# Adafruit_E-Ink_Bonnet_for_Raspberry_Pi_r.net
KiCad netlist of a schematic drawn in EAGLE
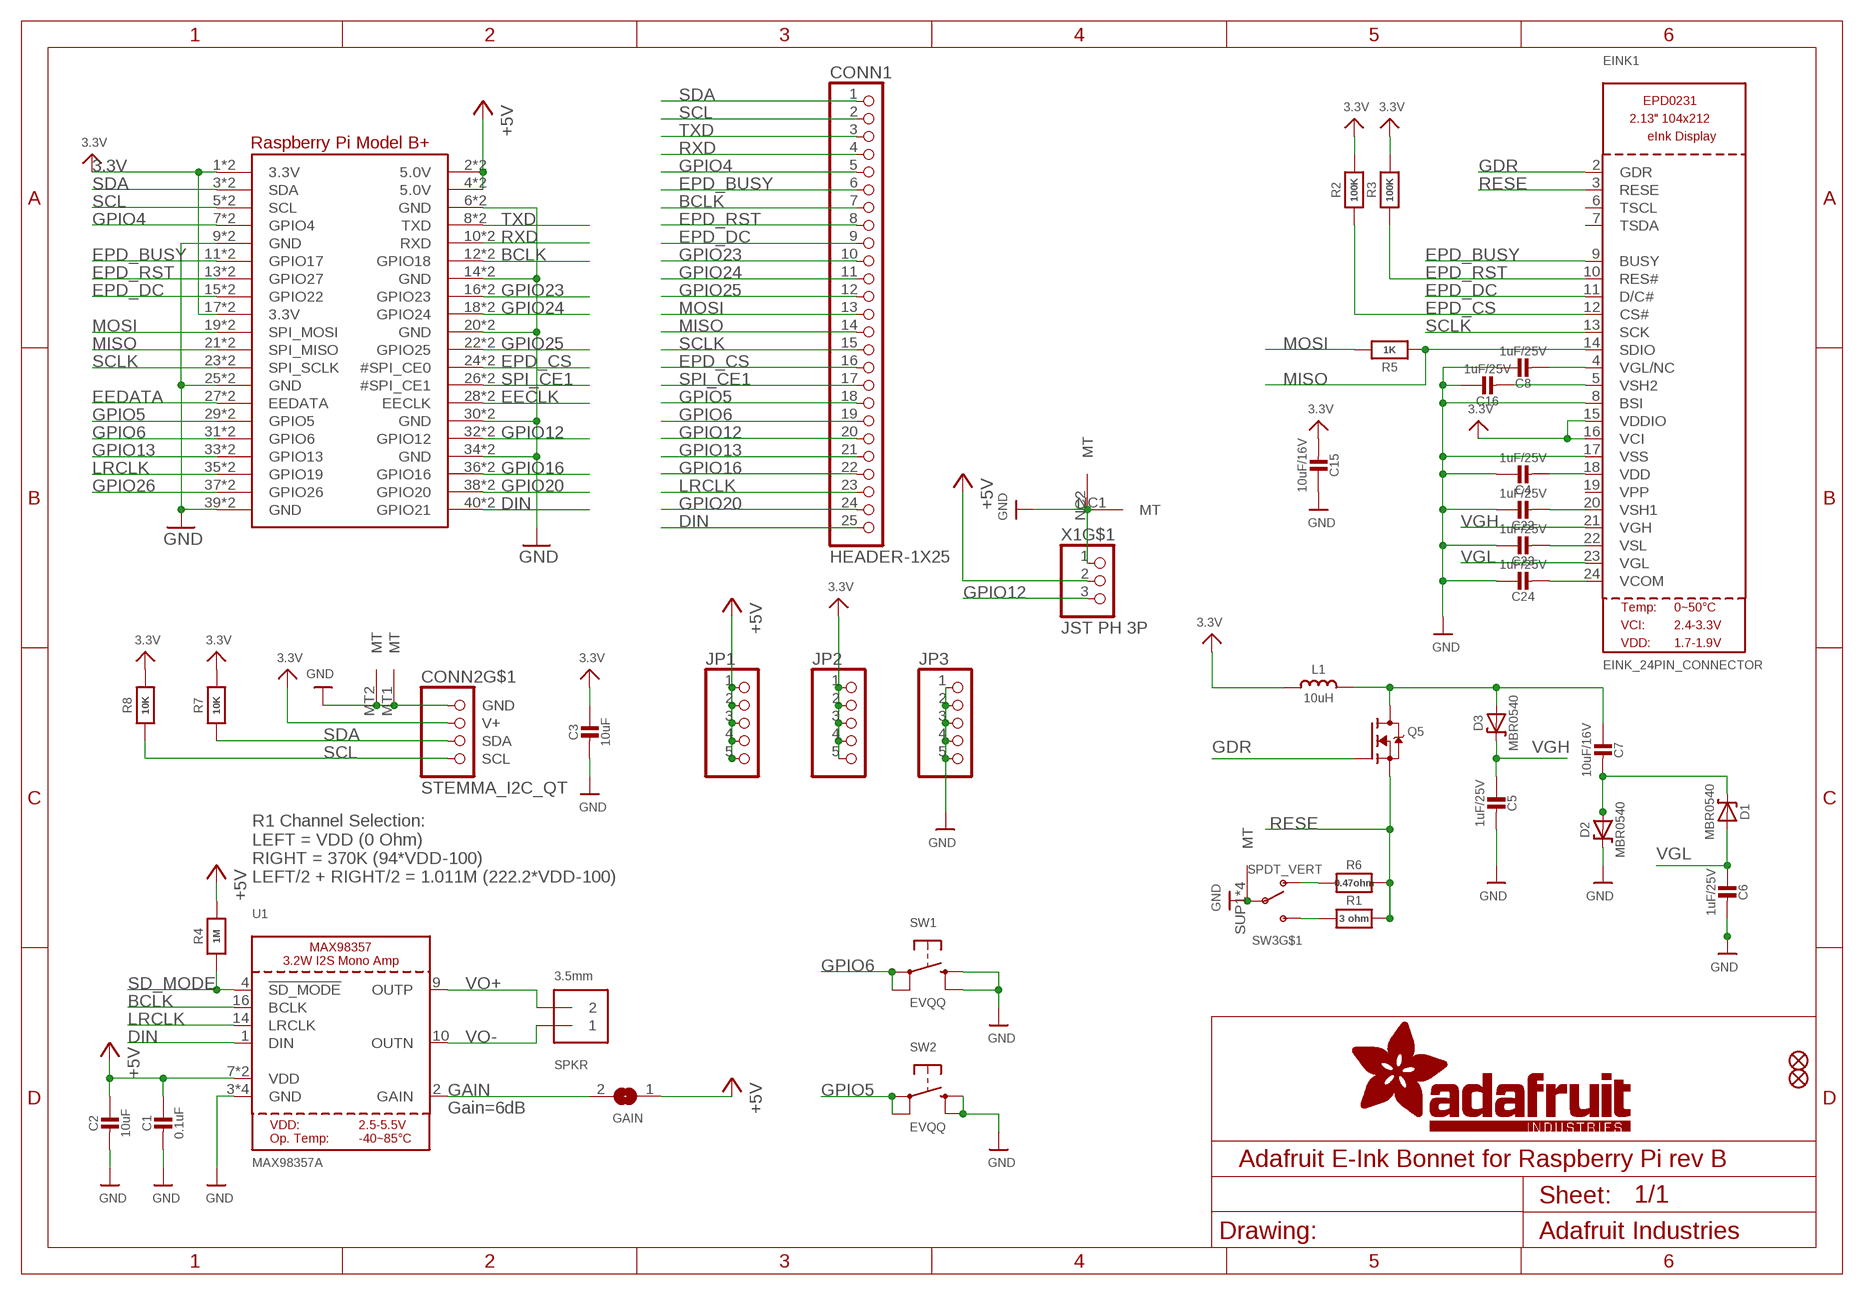
[diagram p0: schematic, sheet 1]

(export (version "E")
  (design (tool "Eeschema 10.0.6"))
  (components
    (comp (ref "C1")
      (value "0.1uF")
      (footprint "eagle-import:0603-NO")
      (libsource (lib "eagle-import") (part "CAP_CERAMIC0603_NO"))
    )
    (comp (ref "C2")
      (value "10uF")
      (footprint "eagle-import:0805-NO")
      (libsource (lib "eagle-import") (part "CAP_CERAMIC0805-NOOUTLINE"))
    )
    (comp (ref "C3")
      (value "10uF")
      (footprint "eagle-import:0805-NO")
      (libsource (lib "eagle-import") (part "CAP_CERAMIC0805-NOOUTLINE"))
    )
    (comp (ref "C4")
      (value "1uF/25V")
      (footprint "eagle-import:0603-NO")
      (libsource (lib "eagle-import") (part "CAP_CERAMIC0603_NO"))
    )
    (comp (ref "C5")
      (value "1uF/25V")
      (footprint "eagle-import:0603-NO")
      (libsource (lib "eagle-import") (part "CAP_CERAMIC0603_NO"))
    )
    (comp (ref "C6")
      (value "1uF/25V")
      (footprint "eagle-import:0603-NO")
      (libsource (lib "eagle-import") (part "CAP_CERAMIC0603_NO"))
    )
    (comp (ref "C7")
      (value "10uF/16V")
      (footprint "eagle-import:0805-NO")
      (libsource (lib "eagle-import") (part "CAP_CERAMIC0805-NOOUTLINE"))
    )
    (comp (ref "C8")
      (value "1uF/25V")
      (footprint "eagle-import:0603-NO")
      (libsource (lib "eagle-import") (part "CAP_CERAMIC0603_NO"))
    )
    (comp (ref "C15")
      (value "10uF/16V")
      (footprint "eagle-import:0805-NO")
      (libsource (lib "eagle-import") (part "CAP_CERAMIC0805-NOOUTLINE"))
    )
    (comp (ref "C16")
      (value "1uF/25V")
      (footprint "eagle-import:0603-NO")
      (libsource (lib "eagle-import") (part "CAP_CERAMIC0603_NO"))
    )
    (comp (ref "C22")
      (value "1uF/25V")
      (footprint "eagle-import:0603-NO")
      (libsource (lib "eagle-import") (part "CAP_CERAMIC0603_NO"))
    )
    (comp (ref "C23")
      (value "1uF/25V")
      (footprint "eagle-import:0603-NO")
      (libsource (lib "eagle-import") (part "CAP_CERAMIC0603_NO"))
    )
    (comp (ref "C24")
      (value "1uF/25V")
      (footprint "eagle-import:0603-NO")
      (libsource (lib "eagle-import") (part "CAP_CERAMIC0603_NO"))
    )
    (comp (ref "CONN1")
      (value "HEADER-1X25")
      (footprint "eagle-import:1X25_ROUND_70MIL")
      (libsource (lib "eagle-import") (part "HEADER-1X25"))
    )
    (comp (ref "CONN2")
      (value "STEMMA_I2C_QT")
      (footprint "eagle-import:JST_SH4")
      (libsource (lib "eagle-import") (part "STEMMA_I2C_QT"))
    )
    (comp (ref "D1")
      (value "MBR0540")
      (footprint "eagle-import:SOD-123")
      (libsource (lib "eagle-import") (part "DIODE-SCHOTTKYSOD-123"))
    )
    (comp (ref "D2")
      (value "MBR0540")
      (footprint "eagle-import:SOD-123")
      (libsource (lib "eagle-import") (part "DIODE-SCHOTTKYSOD-123"))
    )
    (comp (ref "D3")
      (value "MBR0540")
      (footprint "eagle-import:SOD-123")
      (libsource (lib "eagle-import") (part "DIODE-SCHOTTKYSOD-123"))
    )
    (comp (ref "EINK1")
      (value "EINK_24PIN_CONNECTOR")
      (footprint "eagle-import:EINK_24PIN")
      (libsource (lib "eagle-import") (part "EINK_24PIN_CONNECTOR"))
    )
    (comp (ref "FID2")
      (value "FIDUCIAL_1MM")
      (footprint "eagle-import:FIDUCIAL_1MM")
      (libsource (lib "eagle-import") (part "FIDUCIAL_1MM"))
    )
    (comp (ref "FID3")
      (value "FIDUCIAL_1MM")
      (footprint "eagle-import:FIDUCIAL_1MM")
      (libsource (lib "eagle-import") (part "FIDUCIAL_1MM"))
    )
    (comp (ref "GAIN")
      (value "SOLDERJUMPERCLOSED")
      (footprint "eagle-import:SOLDERJUMPER_CLOSEDWIRE")
      (libsource (lib "eagle-import") (part "SOLDERJUMPERCLOSED"))
    )
    (comp (ref "JP1")
      (value "HEADER-1X576MIL")
      (footprint "eagle-import:1X05_ROUND_76")
      (libsource (lib "eagle-import") (part "HEADER-1X576MIL"))
    )
    (comp (ref "JP2")
      (value "HEADER-1X576MIL")
      (footprint "eagle-import:1X05_ROUND_76")
      (libsource (lib "eagle-import") (part "HEADER-1X576MIL"))
    )
    (comp (ref "JP3")
      (value "HEADER-1X576MIL")
      (footprint "eagle-import:1X05_ROUND_76")
      (libsource (lib "eagle-import") (part "HEADER-1X576MIL"))
    )
    (comp (ref "L1")
      (value "10uH")
      (footprint "eagle-import:INDUCTOR_4X4MM_NR401")
      (libsource (lib "eagle-import") (part "INDUCTORNR401"))
    )
    (comp (ref "Q5")
      (value "IRLML0100")
      (footprint "eagle-import:SOT23-3")
      (libsource (lib "eagle-import") (part "IRLML2060TRPBF"))
    )
    (comp (ref "R1")
      (value "3 ohm")
      (footprint "eagle-import:0603-NO")
      (libsource (lib "eagle-import") (part "RESISTOR_0603_NOOUT"))
    )
    (comp (ref "R2")
      (value "100K")
      (footprint "eagle-import:0603-NO")
      (libsource (lib "eagle-import") (part "RESISTOR_0603_NOOUT"))
    )
    (comp (ref "R3")
      (value "100K")
      (footprint "eagle-import:0603-NO")
      (libsource (lib "eagle-import") (part "RESISTOR_0603_NOOUT"))
    )
    (comp (ref "R4")
      (value "1M")
      (footprint "eagle-import:0603-NO")
      (libsource (lib "eagle-import") (part "RESISTOR_0603_NOOUT"))
    )
    (comp (ref "R5")
      (value "1K")
      (footprint "eagle-import:0603-NO")
      (libsource (lib "eagle-import") (part "RESISTOR_0603_NOOUT"))
    )
    (comp (ref "R6")
      (value "0.47ohm")
      (footprint "eagle-import:0603-NO")
      (libsource (lib "eagle-import") (part "RESISTOR_0603_NOOUT"))
    )
    (comp (ref "R7")
      (value "10K")
      (footprint "eagle-import:0603-NO")
      (libsource (lib "eagle-import") (part "RESISTOR_0603_NOOUT"))
    )
    (comp (ref "R8")
      (value "10K")
      (footprint "eagle-import:0603-NO")
      (libsource (lib "eagle-import") (part "RESISTOR_0603_NOOUT"))
    )
    (comp (ref "RPI1")
      (value "RASPBERRYPI_BPLUS_BONNET_THMSMT")
      (footprint "eagle-import:PI_BONNET_THMSMT")
      (libsource (lib "eagle-import") (part "RASPBERRYPI_BPLUS_BONNET_THMSMT"))
    )
    (comp (ref "SPKR")
      (value "3.5mm")
      (footprint "eagle-import:TERMBLOCK_1X2-3.5MM")
      (fields (field (name "ROT") "0"))
      (libsource (lib "eagle-import") (part "TERMBLOCK_1X2_3.5MM"))
    )
    (comp (ref "SW1")
      (value "EVQQ")
      (footprint "eagle-import:6MMX6MM_TACTILE_SMT")
      (libsource (lib "eagle-import") (part "SWITCH_TACT_SMT_6MM"))
    )
    (comp (ref "SW2")
      (value "EVQQ")
      (footprint "eagle-import:6MMX6MM_TACTILE_SMT")
      (libsource (lib "eagle-import") (part "SWITCH_TACT_SMT_6MM"))
    )
    (comp (ref "SW3")
      (value "SPDT_VERT")
      (footprint "eagle-import:SPDT_SMT_SSSS811101")
      (libsource (lib "eagle-import") (part "SWITCH_SPDT"))
    )
    (comp (ref "U1")
      (value "MAX98357A")
      (footprint "eagle-import:QFN16_3MM")
      (libsource (lib "eagle-import") (part "AUDIOAMP_MAX98357"))
    )
    (comp (ref "X1")
      (value "JST PH 3P")
      (footprint "eagle-import:JSTPH3")
      (libsource (lib "eagle-import") (part "CON_JST_PH_3PIN"))
    )
  )
  (nets
    (net (code "1") (name "+5V") (class "Default")
      (node (ref "C1") (pin "1") (pinfunction "1_1") (pintype "passive"))
      (node (ref "C2") (pin "1") (pinfunction "1_1") (pintype "passive"))
      (node (ref "GAIN") (pin "1") (pinfunction "1_1") (pintype "passive"))
      (node (ref "JP1") (pin "1") (pinfunction "1_1") (pintype "passive"))
      (node (ref "JP1") (pin "2") (pinfunction "2_2") (pintype "passive"))
      (node (ref "JP1") (pin "3") (pinfunction "3_3") (pintype "passive"))
      (node (ref "JP1") (pin "4") (pinfunction "4_4") (pintype "passive"))
      (node (ref "JP1") (pin "5") (pinfunction "5_5") (pintype "passive"))
      (node (ref "R4") (pin "2") (pinfunction "2_2") (pintype "passive"))
      (node (ref "RPI1") (pin "2") (pinfunction "5.0V_2") (pintype "power_in"))
      (node (ref "RPI1") (pin "4") (pinfunction "5.0V_4") (pintype "power_in"))
      (node (ref "RPI1") (pin "S2") (pinfunction "5.0V_S2") (pintype "power_in"))
      (node (ref "RPI1") (pin "S4") (pinfunction "5.0V_S4") (pintype "power_in"))
      (node (ref "U1") (pin "7") (pinfunction "VDD_7") (pintype "power_in"))
      (node (ref "U1") (pin "8") (pinfunction "VDD_8") (pintype "power_in"))
      (node (ref "X1") (pin "2") (pinfunction "2_2") (pintype "passive"))
    )
    (net (code "2") (name "/BCLK") (class "Default")
      (node (ref "CONN1") (pin "7") (pinfunction "7_7") (pintype "passive"))
      (node (ref "RPI1") (pin "12") (pinfunction "GPIO18_12") (pintype "bidirectional"))
      (node (ref "RPI1") (pin "S12") (pinfunction "GPIO18_S12") (pintype "bidirectional"))
      (node (ref "U1") (pin "16") (pinfunction "BCLK_16") (pintype "bidirectional"))
    )
    (net (code "3") (name "/DIN") (class "Default")
      (node (ref "CONN1") (pin "25") (pinfunction "25_25") (pintype "passive"))
      (node (ref "RPI1") (pin "40") (pinfunction "GPIO21_40") (pintype "bidirectional"))
      (node (ref "RPI1") (pin "S40") (pinfunction "GPIO21_S40") (pintype "bidirectional"))
      (node (ref "U1") (pin "1") (pinfunction "DIN_1") (pintype "bidirectional"))
    )
    (net (code "4") (name "/EECLK") (class "Default")
      (node (ref "RPI1") (pin "28") (pinfunction "EECLK_28") (pintype "bidirectional"))
      (node (ref "RPI1") (pin "S28") (pinfunction "EECLK_S28") (pintype "bidirectional"))
    )
    (net (code "5") (name "/EEDATA") (class "Default")
      (node (ref "RPI1") (pin "27") (pinfunction "EEDATA_27") (pintype "bidirectional"))
      (node (ref "RPI1") (pin "S27") (pinfunction "EEDATA_S27") (pintype "bidirectional"))
    )
    (net (code "6") (name "/EPD_BUSY") (class "Default")
      (node (ref "CONN1") (pin "6") (pinfunction "6_6") (pintype "passive"))
      (node (ref "EINK1") (pin "9") (pinfunction "BUSY_9") (pintype "output"))
      (node (ref "RPI1") (pin "11") (pinfunction "GPIO17_11") (pintype "bidirectional"))
      (node (ref "RPI1") (pin "S11") (pinfunction "GPIO17_S11") (pintype "bidirectional"))
    )
    (net (code "7") (name "/EPD_CS") (class "Default")
      (node (ref "CONN1") (pin "16") (pinfunction "16_16") (pintype "passive"))
      (node (ref "EINK1") (pin "12") (pinfunction "CS#_12") (pintype "input"))
      (node (ref "R2") (pin "1") (pinfunction "1_1") (pintype "passive"))
      (node (ref "RPI1") (pin "24") (pinfunction "#SPI_CE0_24") (pintype "bidirectional"))
      (node (ref "RPI1") (pin "S24") (pinfunction "#SPI_CE0_S24") (pintype "bidirectional"))
    )
    (net (code "8") (name "/EPD_DC") (class "Default")
      (node (ref "CONN1") (pin "9") (pinfunction "9_9") (pintype "passive"))
      (node (ref "EINK1") (pin "11") (pinfunction "D/C#_11") (pintype "input"))
      (node (ref "RPI1") (pin "15") (pinfunction "GPIO22_15") (pintype "bidirectional"))
      (node (ref "RPI1") (pin "S15") (pinfunction "GPIO22_S15") (pintype "bidirectional"))
    )
    (net (code "9") (name "/EPD_RST") (class "Default")
      (node (ref "CONN1") (pin "8") (pinfunction "8_8") (pintype "passive"))
      (node (ref "EINK1") (pin "10") (pinfunction "RES#_10") (pintype "input"))
      (node (ref "R3") (pin "1") (pinfunction "1_1") (pintype "passive"))
      (node (ref "RPI1") (pin "13") (pinfunction "GPIO27_13") (pintype "bidirectional"))
      (node (ref "RPI1") (pin "S13") (pinfunction "GPIO27_S13") (pintype "bidirectional"))
    )
    (net (code "10") (name "/GAIN") (class "Default")
      (node (ref "GAIN") (pin "2") (pinfunction "2_2") (pintype "passive"))
      (node (ref "U1") (pin "2") (pinfunction "GAIN_2") (pintype "bidirectional"))
    )
    (net (code "11") (name "/GDR") (class "Default")
      (node (ref "EINK1") (pin "2") (pinfunction "GDR_2") (pintype "output"))
      (node (ref "Q5") (pin "1") (pinfunction "G_1") (pintype "bidirectional"))
    )
    (net (code "12") (name "/GPIO4") (class "Default")
      (node (ref "CONN1") (pin "5") (pinfunction "5_5") (pintype "passive"))
      (node (ref "RPI1") (pin "7") (pinfunction "GPIO4_7") (pintype "bidirectional"))
      (node (ref "RPI1") (pin "S7") (pinfunction "GPIO4_S7") (pintype "bidirectional"))
    )
    (net (code "13") (name "/GPIO5") (class "Default")
      (node (ref "CONN1") (pin "18") (pinfunction "18_18") (pintype "passive"))
      (node (ref "RPI1") (pin "29") (pinfunction "GPIO5_29") (pintype "bidirectional"))
      (node (ref "RPI1") (pin "S29") (pinfunction "GPIO5_S29") (pintype "bidirectional"))
      (node (ref "SW2") (pin "A") (pinfunction "P_A") (pintype "passive"))
      (node (ref "SW2") (pin "A'") (pinfunction "P1_A'") (pintype "passive"))
    )
    (net (code "14") (name "/GPIO6") (class "Default")
      (node (ref "CONN1") (pin "19") (pinfunction "19_19") (pintype "passive"))
      (node (ref "RPI1") (pin "31") (pinfunction "GPIO6_31") (pintype "bidirectional"))
      (node (ref "RPI1") (pin "S31") (pinfunction "GPIO6_S31") (pintype "bidirectional"))
      (node (ref "SW1") (pin "A") (pinfunction "P_A") (pintype "passive"))
      (node (ref "SW1") (pin "A'") (pinfunction "P1_A'") (pintype "passive"))
    )
    (net (code "15") (name "/GPIO12") (class "Default")
      (node (ref "CONN1") (pin "20") (pinfunction "20_20") (pintype "passive"))
      (node (ref "RPI1") (pin "32") (pinfunction "GPIO12_32") (pintype "bidirectional"))
      (node (ref "RPI1") (pin "S32") (pinfunction "GPIO12_S32") (pintype "bidirectional"))
      (node (ref "X1") (pin "3") (pinfunction "3_3") (pintype "passive"))
    )
    (net (code "16") (name "/GPIO13") (class "Default")
      (node (ref "CONN1") (pin "21") (pinfunction "21_21") (pintype "passive"))
      (node (ref "RPI1") (pin "33") (pinfunction "GPIO13_33") (pintype "bidirectional"))
      (node (ref "RPI1") (pin "S33") (pinfunction "GPIO13_S33") (pintype "bidirectional"))
    )
    (net (code "17") (name "/GPIO16") (class "Default")
      (node (ref "CONN1") (pin "22") (pinfunction "22_22") (pintype "passive"))
      (node (ref "RPI1") (pin "36") (pinfunction "GPIO16_36") (pintype "bidirectional"))
      (node (ref "RPI1") (pin "S36") (pinfunction "GPIO16_S36") (pintype "bidirectional"))
    )
    (net (code "18") (name "/GPIO20") (class "Default")
      (node (ref "CONN1") (pin "24") (pinfunction "24_24") (pintype "passive"))
      (node (ref "RPI1") (pin "38") (pinfunction "GPIO20_38") (pintype "bidirectional"))
      (node (ref "RPI1") (pin "S38") (pinfunction "GPIO20_S38") (pintype "bidirectional"))
    )
    (net (code "19") (name "/GPIO23") (class "Default")
      (node (ref "CONN1") (pin "10") (pinfunction "10_10") (pintype "passive"))
      (node (ref "RPI1") (pin "16") (pinfunction "GPIO23_16") (pintype "bidirectional"))
      (node (ref "RPI1") (pin "S16") (pinfunction "GPIO23_S16") (pintype "bidirectional"))
    )
    (net (code "20") (name "/GPIO24") (class "Default")
      (node (ref "CONN1") (pin "11") (pinfunction "11_11") (pintype "passive"))
      (node (ref "RPI1") (pin "18") (pinfunction "GPIO24_18") (pintype "bidirectional"))
      (node (ref "RPI1") (pin "S18") (pinfunction "GPIO24_S18") (pintype "bidirectional"))
    )
    (net (code "21") (name "/GPIO25") (class "Default")
      (node (ref "CONN1") (pin "12") (pinfunction "12_12") (pintype "passive"))
      (node (ref "RPI1") (pin "22") (pinfunction "GPIO25_22") (pintype "bidirectional"))
      (node (ref "RPI1") (pin "S22") (pinfunction "GPIO25_S22") (pintype "bidirectional"))
    )
    (net (code "22") (name "/GPIO26") (class "Default")
      (node (ref "RPI1") (pin "37") (pinfunction "GPIO26_37") (pintype "bidirectional"))
      (node (ref "RPI1") (pin "S37") (pinfunction "GPIO26_S37") (pintype "bidirectional"))
    )
    (net (code "23") (name "/LRCLK") (class "Default")
      (node (ref "CONN1") (pin "23") (pinfunction "23_23") (pintype "passive"))
      (node (ref "RPI1") (pin "35") (pinfunction "GPIO19_35") (pintype "bidirectional"))
      (node (ref "RPI1") (pin "S35") (pinfunction "GPIO19_S35") (pintype "bidirectional"))
      (node (ref "U1") (pin "14") (pinfunction "LRCLK_14") (pintype "bidirectional"))
    )
    (net (code "24") (name "/MISO") (class "Default")
      (node (ref "CONN1") (pin "14") (pinfunction "14_14") (pintype "passive"))
      (node (ref "EINK1") (pin "14") (pinfunction "SDIO_14") (pintype "bidirectional"))
      (node (ref "R5") (pin "1") (pinfunction "1_1") (pintype "passive"))
      (node (ref "RPI1") (pin "21") (pinfunction "SPI_MISO_21") (pintype "bidirectional"))
      (node (ref "RPI1") (pin "S21") (pinfunction "SPI_MISO_S21") (pintype "bidirectional"))
    )
    (net (code "25") (name "/MOSI") (class "Default")
      (node (ref "CONN1") (pin "13") (pinfunction "13_13") (pintype "passive"))
      (node (ref "R5") (pin "2") (pinfunction "2_2") (pintype "passive"))
      (node (ref "RPI1") (pin "19") (pinfunction "SPI_MOSI_19") (pintype "bidirectional"))
      (node (ref "RPI1") (pin "S19") (pinfunction "SPI_MOSI_S19") (pintype "bidirectional"))
    )
    (net (code "26") (name "/RESE") (class "Default")
      (node (ref "EINK1") (pin "3") (pinfunction "RESE_3") (pintype "input"))
      (node (ref "Q5") (pin "2") (pinfunction "S_2") (pintype "bidirectional"))
      (node (ref "R1") (pin "1") (pinfunction "1_1") (pintype "passive"))
      (node (ref "R6") (pin "1") (pinfunction "1_1") (pintype "passive"))
    )
    (net (code "27") (name "/RXD") (class "Default")
      (node (ref "CONN1") (pin "4") (pinfunction "4_4") (pintype "passive"))
      (node (ref "RPI1") (pin "10") (pinfunction "RXD_10") (pintype "bidirectional"))
      (node (ref "RPI1") (pin "S10") (pinfunction "RXD_S10") (pintype "bidirectional"))
    )
    (net (code "28") (name "/SCL") (class "Default")
      (node (ref "CONN1") (pin "2") (pinfunction "2_2") (pintype "passive"))
      (node (ref "CONN2") (pin "4") (pinfunction "SCL_4") (pintype "passive"))
      (node (ref "R8") (pin "2") (pinfunction "2_2") (pintype "passive"))
      (node (ref "RPI1") (pin "5") (pinfunction "SCL_5") (pintype "bidirectional"))
      (node (ref "RPI1") (pin "S5") (pinfunction "SCL_S5") (pintype "bidirectional"))
    )
    (net (code "29") (name "/SCLK") (class "Default")
      (node (ref "CONN1") (pin "15") (pinfunction "15_15") (pintype "passive"))
      (node (ref "EINK1") (pin "13") (pinfunction "SCK_13") (pintype "bidirectional"))
      (node (ref "RPI1") (pin "23") (pinfunction "SPI_SCLK_23") (pintype "bidirectional"))
      (node (ref "RPI1") (pin "S23") (pinfunction "SPI_SCLK_S23") (pintype "bidirectional"))
    )
    (net (code "30") (name "/SDA") (class "Default")
      (node (ref "CONN1") (pin "1") (pinfunction "1_1") (pintype "passive"))
      (node (ref "CONN2") (pin "3") (pinfunction "SDA_3") (pintype "passive"))
      (node (ref "R7") (pin "2") (pinfunction "2_2") (pintype "passive"))
      (node (ref "RPI1") (pin "3") (pinfunction "SDA_3") (pintype "bidirectional"))
      (node (ref "RPI1") (pin "S3") (pinfunction "SDA_S3") (pintype "bidirectional"))
    )
    (net (code "31") (name "/SD_MODE") (class "Default")
      (node (ref "R4") (pin "1") (pinfunction "1_1") (pintype "passive"))
      (node (ref "U1") (pin "4") (pinfunction "~{SD_MODE}_4") (pintype "bidirectional"))
    )
    (net (code "32") (name "/SPI_CE1") (class "Default")
      (node (ref "CONN1") (pin "17") (pinfunction "17_17") (pintype "passive"))
      (node (ref "RPI1") (pin "26") (pinfunction "#SPI_CE1_26") (pintype "bidirectional"))
      (node (ref "RPI1") (pin "S26") (pinfunction "#SPI_CE1_S26") (pintype "bidirectional"))
    )
    (net (code "33") (name "/TXD") (class "Default")
      (node (ref "CONN1") (pin "3") (pinfunction "3_3") (pintype "passive"))
      (node (ref "RPI1") (pin "8") (pinfunction "TXD_8") (pintype "bidirectional"))
      (node (ref "RPI1") (pin "S8") (pinfunction "TXD_S8") (pintype "bidirectional"))
    )
    (net (code "34") (name "/VGH") (class "Default")
      (node (ref "C5") (pin "1") (pinfunction "1_1") (pintype "passive"))
      (node (ref "D3") (pin "C") (pinfunction "C_C") (pintype "passive"))
      (node (ref "EINK1") (pin "21") (pinfunction "VGH_21") (pintype "passive"))
    )
    (net (code "35") (name "/VGL") (class "Default")
      (node (ref "C6") (pin "1") (pinfunction "1_1") (pintype "passive"))
      (node (ref "D1") (pin "A") (pinfunction "A_A") (pintype "passive"))
      (node (ref "EINK1") (pin "23") (pinfunction "VGL_23") (pintype "passive"))
    )
    (net (code "36") (name "/VO+") (class "Default")
      (node (ref "SPKR") (pin "2") (pinfunction "2_2") (pintype "passive"))
      (node (ref "U1") (pin "9") (pinfunction "OUTP_9") (pintype "output"))
    )
    (net (code "37") (name "/VO-") (class "Default")
      (node (ref "SPKR") (pin "1") (pinfunction "1_1") (pintype "passive"))
      (node (ref "U1") (pin "10") (pinfunction "OUTN_10") (pintype "output"))
    )
    (net (code "38") (name "3.3V") (class "Default")
      (node (ref "C15") (pin "2") (pinfunction "2_2") (pintype "passive"))
      (node (ref "C3") (pin "1") (pinfunction "1_1") (pintype "passive"))
      (node (ref "CONN2") (pin "2") (pinfunction "V+_2") (pintype "passive"))
      (node (ref "EINK1") (pin "15") (pinfunction "VDDIO_15") (pintype "power_in"))
      (node (ref "EINK1") (pin "16") (pinfunction "VCI_16") (pintype "power_in"))
      (node (ref "JP2") (pin "1") (pinfunction "1_1") (pintype "passive"))
      (node (ref "JP2") (pin "2") (pinfunction "2_2") (pintype "passive"))
      (node (ref "JP2") (pin "3") (pinfunction "3_3") (pintype "passive"))
      (node (ref "JP2") (pin "4") (pinfunction "4_4") (pintype "passive"))
      (node (ref "JP2") (pin "5") (pinfunction "5_5") (pintype "passive"))
      (node (ref "L1") (pin "P$2") (pinfunction "2_P$2") (pintype "passive"))
      (node (ref "R2") (pin "2") (pinfunction "2_2") (pintype "passive"))
      (node (ref "R3") (pin "2") (pinfunction "2_2") (pintype "passive"))
      (node (ref "R7") (pin "1") (pinfunction "1_1") (pintype "passive"))
      (node (ref "R8") (pin "1") (pinfunction "1_1") (pintype "passive"))
      (node (ref "RPI1") (pin "1") (pinfunction "3.3V_1") (pintype "power_in"))
      (node (ref "RPI1") (pin "17") (pinfunction "3.3V_17") (pintype "power_in"))
      (node (ref "RPI1") (pin "S1") (pinfunction "3.3V_S1") (pintype "power_in"))
      (node (ref "RPI1") (pin "S17") (pinfunction "3.3V_S17") (pintype "power_in"))
    )
    (net (code "39") (name "GND") (class "Default")
      (node (ref "C1") (pin "2") (pinfunction "2_2") (pintype "passive"))
      (node (ref "C15") (pin "1") (pinfunction "1_1") (pintype "passive"))
      (node (ref "C16") (pin "1") (pinfunction "1_1") (pintype "passive"))
      (node (ref "C2") (pin "2") (pinfunction "2_2") (pintype "passive"))
      (node (ref "C22") (pin "1") (pinfunction "1_1") (pintype "passive"))
      (node (ref "C23") (pin "1") (pinfunction "1_1") (pintype "passive"))
      (node (ref "C24") (pin "1") (pinfunction "1_1") (pintype "passive"))
      (node (ref "C3") (pin "2") (pinfunction "2_2") (pintype "passive"))
      (node (ref "C4") (pin "1") (pinfunction "1_1") (pintype "passive"))
      (node (ref "C5") (pin "2") (pinfunction "2_2") (pintype "passive"))
      (node (ref "C6") (pin "2") (pinfunction "2_2") (pintype "passive"))
      (node (ref "C8") (pin "1") (pinfunction "1_1") (pintype "passive"))
      (node (ref "CONN2") (pin "1") (pinfunction "GND_1") (pintype "passive"))
      (node (ref "CONN2") (pin "MT1") (pinfunction "MT_MT1") (pintype "bidirectional"))
      (node (ref "CONN2") (pin "MT2") (pinfunction "MT_MT2") (pintype "bidirectional"))
      (node (ref "D2") (pin "C") (pinfunction "C_C") (pintype "passive"))
      (node (ref "EINK1") (pin "17") (pinfunction "VSS_17") (pintype "power_in"))
      (node (ref "EINK1") (pin "8") (pinfunction "BSI_8") (pintype "input"))
      (node (ref "JP3") (pin "1") (pinfunction "1_1") (pintype "passive"))
      (node (ref "JP3") (pin "2") (pinfunction "2_2") (pintype "passive"))
      (node (ref "JP3") (pin "3") (pinfunction "3_3") (pintype "passive"))
      (node (ref "JP3") (pin "4") (pinfunction "4_4") (pintype "passive"))
      (node (ref "JP3") (pin "5") (pinfunction "5_5") (pintype "passive"))
      (node (ref "RPI1") (pin "14") (pinfunction "GND_14") (pintype "power_in"))
      (node (ref "RPI1") (pin "20") (pinfunction "GND_20") (pintype "power_in"))
      (node (ref "RPI1") (pin "25") (pinfunction "GND_25") (pintype "power_in"))
      (node (ref "RPI1") (pin "30") (pinfunction "GND_30") (pintype "power_in"))
      (node (ref "RPI1") (pin "34") (pinfunction "GND_34") (pintype "power_in"))
      (node (ref "RPI1") (pin "39") (pinfunction "GND_39") (pintype "power_in"))
      (node (ref "RPI1") (pin "6") (pinfunction "GND_6") (pintype "power_in"))
      (node (ref "RPI1") (pin "9") (pinfunction "GND_9") (pintype "power_in"))
      (node (ref "RPI1") (pin "S14") (pinfunction "GND_S14") (pintype "power_in"))
      (node (ref "RPI1") (pin "S20") (pinfunction "GND_S20") (pintype "power_in"))
      (node (ref "RPI1") (pin "S25") (pinfunction "GND_S25") (pintype "power_in"))
      (node (ref "RPI1") (pin "S30") (pinfunction "GND_S30") (pintype "power_in"))
      (node (ref "RPI1") (pin "S34") (pinfunction "GND_S34") (pintype "power_in"))
      (node (ref "RPI1") (pin "S39") (pinfunction "GND_S39") (pintype "power_in"))
      (node (ref "RPI1") (pin "S6") (pinfunction "GND_S6") (pintype "power_in"))
      (node (ref "RPI1") (pin "S9") (pinfunction "GND_S9") (pintype "power_in"))
      (node (ref "SW1") (pin "B") (pinfunction "S_B") (pintype "passive"))
      (node (ref "SW1") (pin "B'") (pinfunction "S1_B'") (pintype "passive"))
      (node (ref "SW2") (pin "B") (pinfunction "S_B") (pintype "passive"))
      (node (ref "SW2") (pin "B'") (pinfunction "S1_B'") (pintype "passive"))
      (node (ref "SW3") (pin "B") (pinfunction "P_B") (pintype "passive"))
      (node (ref "SW3") (pin "SUP1") (pinfunction "MT_SUP1") (pintype "bidirectional"))
      (node (ref "SW3") (pin "SUP2") (pinfunction "MT_SUP2") (pintype "bidirectional"))
      (node (ref "SW3") (pin "SUP3") (pinfunction "MT_SUP3") (pintype "bidirectional"))
      (node (ref "SW3") (pin "SUP4") (pinfunction "MT_SUP4") (pintype "bidirectional"))
      (node (ref "U1") (pin "11") (pinfunction "GND_11") (pintype "power_in"))
      (node (ref "U1") (pin "15") (pinfunction "GND_15") (pintype "power_in"))
      (node (ref "U1") (pin "3") (pinfunction "GND_3") (pintype "power_in"))
      (node (ref "U1") (pin "THERMAL") (pinfunction "GND_THERMAL") (pintype "power_in"))
      (node (ref "X1") (pin "1") (pinfunction "1_1") (pintype "passive"))
      (node (ref "X1") (pin "NC1") (pinfunction "MT_NC1") (pintype "bidirectional"))
      (node (ref "X1") (pin "NC2") (pinfunction "MT_NC2") (pintype "bidirectional"))
    )
    (net (code "40") (name "Net-(C7-Pad2)") (class "Default")
      (node (ref "C7") (pin "2") (pinfunction "2_2") (pintype "passive"))
      (node (ref "D1") (pin "C") (pinfunction "C_C") (pintype "passive"))
      (node (ref "D2") (pin "A") (pinfunction "A_A") (pintype "passive"))
    )
    (net (code "41") (name "Net-(EINK1-VCOM)") (class "Default")
      (node (ref "C24") (pin "2") (pinfunction "2_2") (pintype "passive"))
      (node (ref "EINK1") (pin "24") (pinfunction "VCOM_24") (pintype "passive"))
    )
    (net (code "42") (name "Net-(EINK1-VDD)") (class "Default")
      (node (ref "C4") (pin "2") (pinfunction "2_2") (pintype "passive"))
      (node (ref "EINK1") (pin "18") (pinfunction "VDD_18") (pintype "passive"))
    )
    (net (code "43") (name "Net-(EINK1-VGL{slash}NC)") (class "Default")
      (node (ref "C8") (pin "2") (pinfunction "2_2") (pintype "passive"))
      (node (ref "EINK1") (pin "4") (pinfunction "VGL/NC_4") (pintype "bidirectional"))
    )
    (net (code "44") (name "Net-(EINK1-VSH1)") (class "Default")
      (node (ref "C22") (pin "2") (pinfunction "2_2") (pintype "passive"))
      (node (ref "EINK1") (pin "20") (pinfunction "VSH1_20") (pintype "passive"))
    )
    (net (code "45") (name "Net-(EINK1-VSH2)") (class "Default")
      (node (ref "C16") (pin "2") (pinfunction "2_2") (pintype "passive"))
      (node (ref "EINK1") (pin "5") (pinfunction "VSH2_5") (pintype "passive"))
    )
    (net (code "46") (name "Net-(EINK1-VSL)") (class "Default")
      (node (ref "C23") (pin "2") (pinfunction "2_2") (pintype "passive"))
      (node (ref "EINK1") (pin "22") (pinfunction "VSL_22") (pintype "passive"))
    )
    (net (code "47") (name "Net-(L1-1)") (class "Default")
      (node (ref "C7") (pin "1") (pinfunction "1_1") (pintype "passive"))
      (node (ref "D3") (pin "A") (pinfunction "A_A") (pintype "passive"))
      (node (ref "L1") (pin "P$1") (pinfunction "1_P$1") (pintype "passive"))
      (node (ref "Q5") (pin "3") (pinfunction "D_3") (pintype "bidirectional"))
    )
    (net (code "48") (name "Net-(SW3A-O)") (class "Default")
      (node (ref "R6") (pin "2") (pinfunction "2_2") (pintype "passive"))
      (node (ref "SW3") (pin "A") (pinfunction "O_A") (pintype "passive"))
    )
    (net (code "49") (name "Net-(SW3A-S)") (class "Default")
      (node (ref "R1") (pin "2") (pinfunction "2_2") (pintype "passive"))
      (node (ref "SW3") (pin "C") (pinfunction "S_C") (pintype "passive"))
    )
    (net (code "50") (name "unconnected-(EINK1-TSCL-Pad6)") (class "Default")
      (node (ref "EINK1") (pin "6") (pinfunction "TSCL_6") (pintype "output"))
    )
    (net (code "51") (name "unconnected-(EINK1-TSDA-Pad7)") (class "Default")
      (node (ref "EINK1") (pin "7") (pinfunction "TSDA_7") (pintype "bidirectional"))
    )
    (net (code "52") (name "unconnected-(EINK1-VPP-Pad19)") (class "Default")
      (node (ref "EINK1") (pin "19") (pinfunction "VPP_19") (pintype "passive"))
    )
  )
)
